# I2C_10p_header.net
KiCad netlist of a schematic drawn in EAGLE
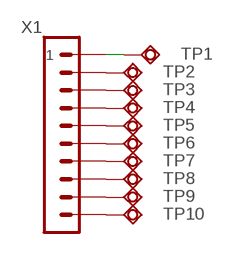
[diagram p0: schematic, sheet 1]

(export (version "E")
  (design (tool "Eeschema 10.0.6"))
  (components
    (comp (ref "TP1")
      (value "PAD1.5X3.0")
      (footprint "eagle-import:PAD1.5X3.0")
      (libsource (lib "eagle-import") (part "PAD1.5X3.0"))
    )
    (comp (ref "TP2")
      (value "PAD1.5X3.0")
      (footprint "eagle-import:PAD1.5X3.0")
      (libsource (lib "eagle-import") (part "PAD1.5X3.0"))
    )
    (comp (ref "TP3")
      (value "PAD1.5X3.0")
      (footprint "eagle-import:PAD1.5X3.0")
      (libsource (lib "eagle-import") (part "PAD1.5X3.0"))
    )
    (comp (ref "TP4")
      (value "PAD1.5X3.0")
      (footprint "eagle-import:PAD1.5X3.0")
      (libsource (lib "eagle-import") (part "PAD1.5X3.0"))
    )
    (comp (ref "TP5")
      (value "PAD1.5X3.0")
      (footprint "eagle-import:PAD1.5X3.0")
      (libsource (lib "eagle-import") (part "PAD1.5X3.0"))
    )
    (comp (ref "TP6")
      (value "PAD1.5X3.0")
      (footprint "eagle-import:PAD1.5X3.0")
      (libsource (lib "eagle-import") (part "PAD1.5X3.0"))
    )
    (comp (ref "TP7")
      (value "PAD1.5X3.0")
      (footprint "eagle-import:PAD1.5X3.0")
      (libsource (lib "eagle-import") (part "PAD1.5X3.0"))
    )
    (comp (ref "TP8")
      (value "PAD1.5X3.0")
      (footprint "eagle-import:PAD1.5X3.0")
      (libsource (lib "eagle-import") (part "PAD1.5X3.0"))
    )
    (comp (ref "TP9")
      (value "PAD1.5X3.0")
      (footprint "eagle-import:PAD1.5X3.0")
      (libsource (lib "eagle-import") (part "PAD1.5X3.0"))
    )
    (comp (ref "TP10")
      (value "PAD1.5X3.0")
      (footprint "eagle-import:PAD1.5X3.0")
      (libsource (lib "eagle-import") (part "PAD1.5X3.0"))
    )
    (comp (ref "X1")
      (value "FFC_10PV")
      (footprint "eagle-import:FFC_1X10_VERTICAL")
      (libsource (lib "eagle-import") (part "FFC_10PV"))
    )
  )
  (nets
    (net (code "1") (name "Net-(X1A-1)") (class "Default")
      (node (ref "TP1") (pin "P$1") (pinfunction "P$1_P$1") (pintype "bidirectional"))
      (node (ref "X1") (pin "P$1") (pinfunction "1_P$1") (pintype "passive"))
    )
    (net (code "2") (name "Net-(X1A-2)") (class "Default")
      (node (ref "TP2") (pin "P$1") (pinfunction "P$1_P$1") (pintype "bidirectional"))
      (node (ref "X1") (pin "P$2") (pinfunction "2_P$2") (pintype "passive"))
    )
    (net (code "3") (name "Net-(X1A-3)") (class "Default")
      (node (ref "TP3") (pin "P$1") (pinfunction "P$1_P$1") (pintype "bidirectional"))
      (node (ref "X1") (pin "P$3") (pinfunction "3_P$3") (pintype "passive"))
    )
    (net (code "4") (name "Net-(X1A-4)") (class "Default")
      (node (ref "TP4") (pin "P$1") (pinfunction "P$1_P$1") (pintype "bidirectional"))
      (node (ref "X1") (pin "P$4") (pinfunction "4_P$4") (pintype "passive"))
    )
    (net (code "5") (name "Net-(X1A-5)") (class "Default")
      (node (ref "TP5") (pin "P$1") (pinfunction "P$1_P$1") (pintype "bidirectional"))
      (node (ref "X1") (pin "P$5") (pinfunction "5_P$5") (pintype "passive"))
    )
    (net (code "6") (name "Net-(X1A-6)") (class "Default")
      (node (ref "TP6") (pin "P$1") (pinfunction "P$1_P$1") (pintype "bidirectional"))
      (node (ref "X1") (pin "P$6") (pinfunction "6_P$6") (pintype "passive"))
    )
    (net (code "7") (name "Net-(X1A-7)") (class "Default")
      (node (ref "TP7") (pin "P$1") (pinfunction "P$1_P$1") (pintype "bidirectional"))
      (node (ref "X1") (pin "P$7") (pinfunction "7_P$7") (pintype "passive"))
    )
    (net (code "8") (name "Net-(X1A-8)") (class "Default")
      (node (ref "TP8") (pin "P$1") (pinfunction "P$1_P$1") (pintype "bidirectional"))
      (node (ref "X1") (pin "P$8") (pinfunction "8_P$8") (pintype "passive"))
    )
    (net (code "9") (name "Net-(X1A-9)") (class "Default")
      (node (ref "TP9") (pin "P$1") (pinfunction "P$1_P$1") (pintype "bidirectional"))
      (node (ref "X1") (pin "P$9") (pinfunction "9_P$9") (pintype "passive"))
    )
    (net (code "10") (name "Net-(X1A-10)") (class "Default")
      (node (ref "TP10") (pin "P$1") (pinfunction "P$1_P$1") (pintype "bidirectional"))
      (node (ref "X1") (pin "P$10") (pinfunction "10_P$10") (pintype "passive"))
    )
  )
)
